# VibrationLights.net
KiCad netlist of a schematic drawn in EAGLE
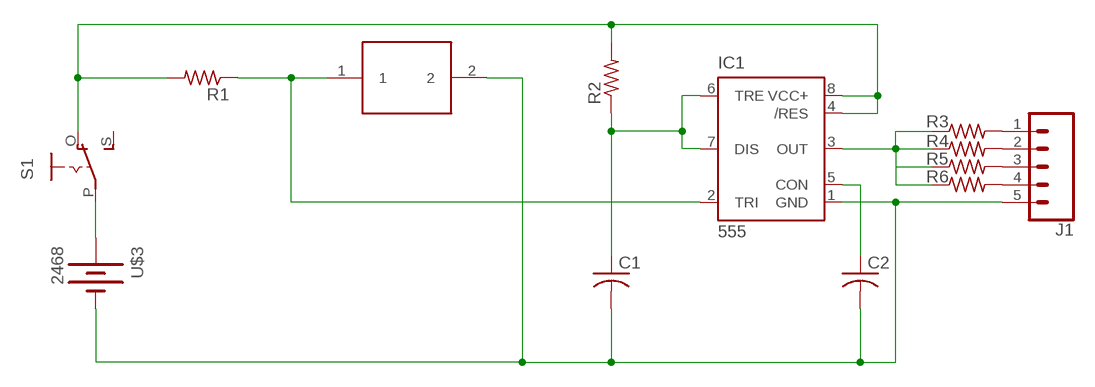
[diagram p0: schematic, sheet 1]

(export (version "E")
  (design (tool "Eeschema 10.0.6"))
  (components
    (comp (ref "C1")
      (value "C-US050-045X075")
      (footprint "eagle-import:C050-045X075")
      (libsource (lib "eagle-import") (part "C-US050-045X075"))
    )
    (comp (ref "C2")
      (value "C-US025-050X050")
      (footprint "eagle-import:C025-050X050")
      (libsource (lib "eagle-import") (part "C-US025-050X050"))
    )
    (comp (ref "IC1")
      (value "555")
      (footprint "eagle-import:DIP08")
      (libsource (lib "eagle-import") (part "555P"))
    )
    (comp (ref "J1")
      (value "CONN_05PTH_LONGPADS")
      (footprint "eagle-import:1X05_LONGPADS")
      (libsource (lib "eagle-import") (part "CONN_05PTH_LONGPADS"))
    )
    (comp (ref "R1")
      (value "R-US_0204/5")
      (footprint "eagle-import:0204_5")
      (libsource (lib "eagle-import") (part "R-US_0204/5"))
    )
    (comp (ref "R2")
      (value "R-US_0204/5")
      (footprint "eagle-import:0204_5")
      (libsource (lib "eagle-import") (part "R-US_0204/5"))
    )
    (comp (ref "R3")
      (value "R-US_0204/5")
      (footprint "eagle-import:0204_5")
      (libsource (lib "eagle-import") (part "R-US_0204/5"))
    )
    (comp (ref "R4")
      (value "R-US_0204/5")
      (footprint "eagle-import:0204_5")
      (libsource (lib "eagle-import") (part "R-US_0204/5"))
    )
    (comp (ref "R5")
      (value "R-US_0204/5")
      (footprint "eagle-import:0204_5")
      (libsource (lib "eagle-import") (part "R-US_0204/5"))
    )
    (comp (ref "R6")
      (value "R-US_0204/5")
      (footprint "eagle-import:0204_5")
      (libsource (lib "eagle-import") (part "R-US_0204/5"))
    )
    (comp (ref "S1")
      (value "EG1218S")
      (footprint "eagle-import:EG1218")
      (libsource (lib "eagle-import") (part "EG1218S"))
    )
    (comp (ref "U$1")
      (value "SW-18010P")
      (footprint "eagle-import:SW-18010P")
      (libsource (lib "eagle-import") (part "SW-18010P"))
    )
    (comp (ref "U$3")
      (value "2468")
      (footprint "eagle-import:2468")
      (libsource (lib "eagle-import") (part "2468"))
    )
  )
  (nets
    (net (code "1") (name "Net-(IC1-CON)") (class "Default")
      (node (ref "C2") (pin "1") (pinfunction "1_1") (pintype "passive"))
      (node (ref "IC1") (pin "5") (pinfunction "CON_5") (pintype "input"))
    )
    (net (code "2") (name "Net-(IC1-DIS)") (class "Default")
      (node (ref "C1") (pin "1") (pinfunction "1_1") (pintype "passive"))
      (node (ref "IC1") (pin "6") (pinfunction "TRE_6") (pintype "input"))
      (node (ref "IC1") (pin "7") (pinfunction "DIS_7") (pintype "input"))
      (node (ref "R2") (pin "1") (pinfunction "1_1") (pintype "passive"))
    )
    (net (code "3") (name "Net-(IC1-GND)") (class "Default")
      (node (ref "C1") (pin "2") (pinfunction "2_2") (pintype "passive"))
      (node (ref "C2") (pin "2") (pinfunction "2_2") (pintype "passive"))
      (node (ref "IC1") (pin "1") (pinfunction "GND_1") (pintype "power_in"))
      (node (ref "J1") (pin "5") (pinfunction "5_5") (pintype "passive"))
      (node (ref "U$1") (pin "2") (pinfunction "2_2") (pintype "bidirectional"))
      (node (ref "U$3") (pin "NEG") (pinfunction "-_NEG") (pintype "power_in"))
    )
    (net (code "4") (name "Net-(IC1-OUT)") (class "Default")
      (node (ref "IC1") (pin "3") (pinfunction "OUT_3") (pintype "output"))
      (node (ref "R3") (pin "1") (pinfunction "1_1") (pintype "passive"))
      (node (ref "R4") (pin "1") (pinfunction "1_1") (pintype "passive"))
      (node (ref "R5") (pin "1") (pinfunction "1_1") (pintype "passive"))
      (node (ref "R6") (pin "1") (pinfunction "1_1") (pintype "passive"))
    )
    (net (code "5") (name "Net-(IC1-TRI)") (class "Default")
      (node (ref "IC1") (pin "2") (pinfunction "TRI_2") (pintype "input"))
      (node (ref "R1") (pin "1") (pinfunction "1_1") (pintype "passive"))
      (node (ref "U$1") (pin "1") (pinfunction "1_1") (pintype "bidirectional"))
    )
    (net (code "6") (name "Net-(IC1-VCC+)") (class "Default")
      (node (ref "IC1") (pin "4") (pinfunction "/RES_4") (pintype "input"))
      (node (ref "IC1") (pin "8") (pinfunction "VCC+_8") (pintype "power_in"))
      (node (ref "R1") (pin "2") (pinfunction "2_2") (pintype "passive"))
      (node (ref "R2") (pin "2") (pinfunction "2_2") (pintype "passive"))
      (node (ref "S1") (pin "O") (pinfunction "O_O") (pintype "passive"))
    )
    (net (code "7") (name "Net-(J1-Pad1)") (class "Default")
      (node (ref "J1") (pin "1") (pinfunction "1_1") (pintype "passive"))
      (node (ref "R3") (pin "2") (pinfunction "2_2") (pintype "passive"))
    )
    (net (code "8") (name "Net-(J1-Pad2)") (class "Default")
      (node (ref "J1") (pin "2") (pinfunction "2_2") (pintype "passive"))
      (node (ref "R4") (pin "2") (pinfunction "2_2") (pintype "passive"))
    )
    (net (code "9") (name "Net-(J1-Pad3)") (class "Default")
      (node (ref "J1") (pin "3") (pinfunction "3_3") (pintype "passive"))
      (node (ref "R5") (pin "2") (pinfunction "2_2") (pintype "passive"))
    )
    (net (code "10") (name "Net-(J1-Pad4)") (class "Default")
      (node (ref "J1") (pin "4") (pinfunction "4_4") (pintype "passive"))
      (node (ref "R6") (pin "2") (pinfunction "2_2") (pintype "passive"))
    )
    (net (code "11") (name "Net-(U$3-+)") (class "Default")
      (node (ref "S1") (pin "P") (pinfunction "P_P") (pintype "passive"))
      (node (ref "U$3") (pin "POS") (pinfunction "+_POS") (pintype "power_in"))
    )
    (net (code "12") (name "unconnected-(S1-PadS)") (class "Default")
      (node (ref "S1") (pin "S") (pinfunction "S_S") (pintype "passive"))
    )
  )
)
